# SK8_ver3.net
KiCad netlist of a schematic drawn in EAGLE
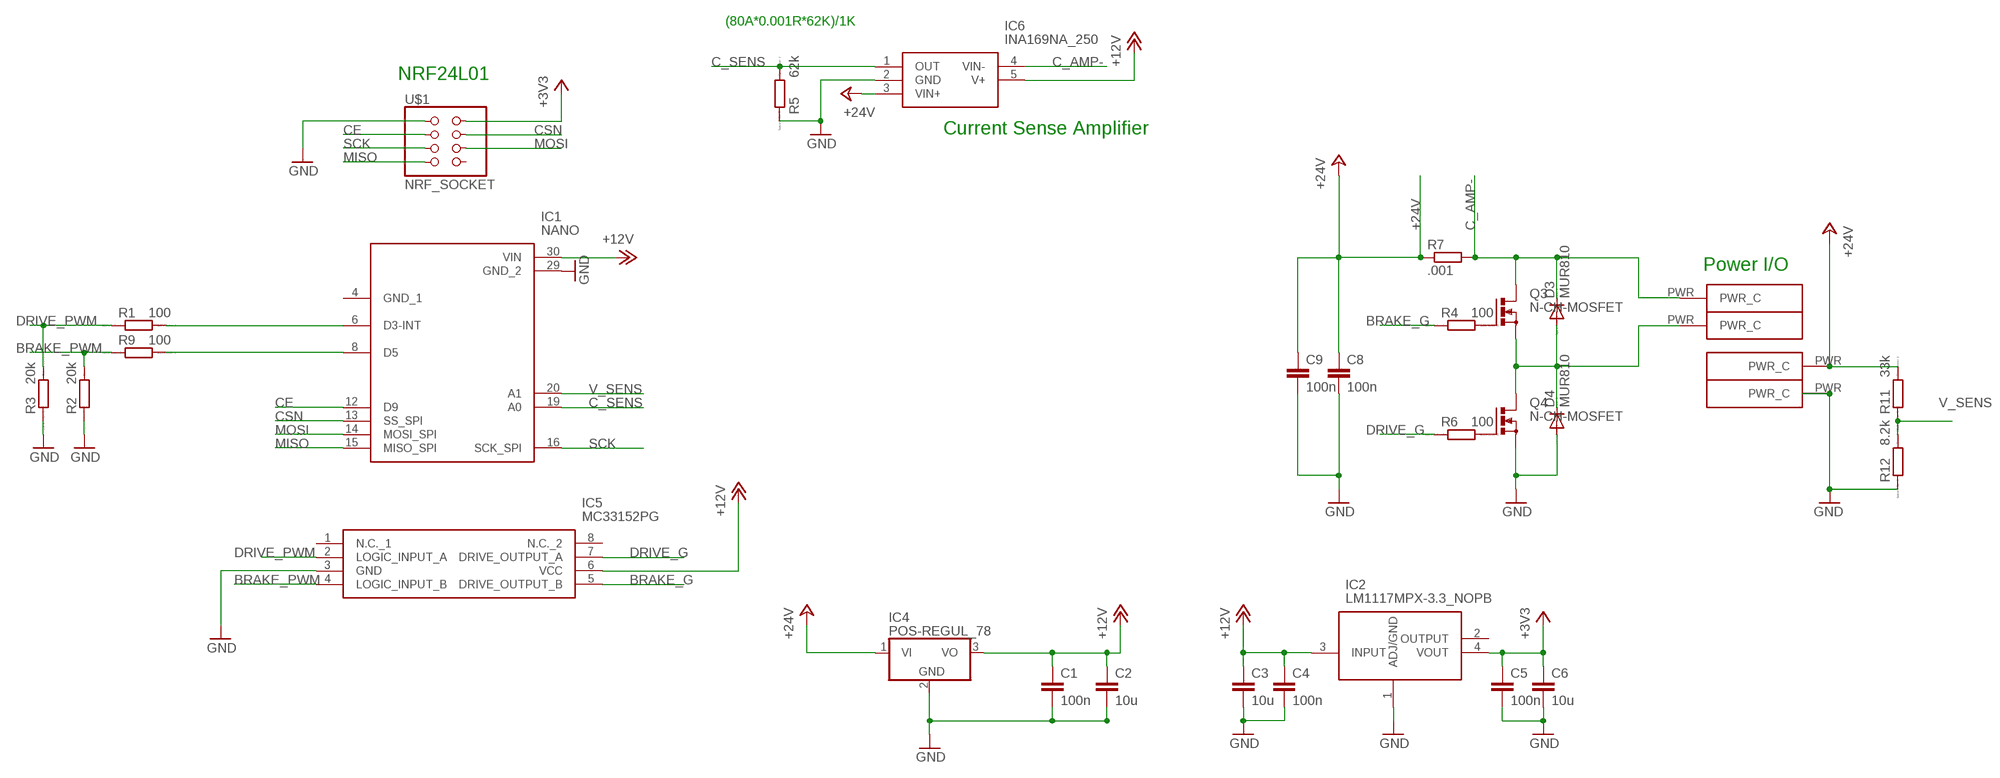
[diagram p0: schematic, sheet 1]

(export (version "E")
  (design (tool "Eeschema 10.0.6"))
  (components
    (comp (ref "C1")
      (value "100n")
      (footprint "eagle-import:C1206")
      (libsource (lib "eagle-import") (part "C-EUC1206"))
    )
    (comp (ref "C2")
      (value "10u")
      (footprint "eagle-import:C1206")
      (libsource (lib "eagle-import") (part "C-EUC1206"))
    )
    (comp (ref "C3")
      (value "10u")
      (footprint "eagle-import:C1206")
      (libsource (lib "eagle-import") (part "C-EUC1206"))
    )
    (comp (ref "C4")
      (value "100n")
      (footprint "eagle-import:C1206")
      (libsource (lib "eagle-import") (part "C-EUC1206"))
    )
    (comp (ref "C5")
      (value "100n")
      (footprint "eagle-import:C1206")
      (libsource (lib "eagle-import") (part "C-EUC1206"))
    )
    (comp (ref "C6")
      (value "10u")
      (footprint "eagle-import:C1206")
      (libsource (lib "eagle-import") (part "C-EUC1206"))
    )
    (comp (ref "C8")
      (value "100n")
      (footprint "eagle-import:C1206")
      (libsource (lib "eagle-import") (part "C-EUC1206"))
    )
    (comp (ref "C9")
      (value "100n")
      (footprint "eagle-import:C1206")
      (libsource (lib "eagle-import") (part "C-EUC1206"))
    )
    (comp (ref "D3")
      (value "MUR810")
      (footprint "eagle-import:TO220ACS")
      (libsource (lib "eagle-import") (part "MUR810"))
    )
    (comp (ref "D4")
      (value "MUR810")
      (footprint "eagle-import:TO220ACS")
      (libsource (lib "eagle-import") (part "MUR810"))
    )
    (comp (ref "IC1")
      (value "NANO")
      (footprint "eagle-import:DIP1524W102P254L4318H762Q30N")
      (fields (field (name "ARROW_PART_NUMBER") "Nano") (field (name "RS_PART_NUMBER") "6961667"))
      (libsource (lib "eagle-import") (part "NANO"))
    )
    (comp (ref "IC2")
      (value "LM1117MPX-3.3_NOPB")
      (footprint "eagle-import:SOT230P700X180-4N")
      (fields (field (name "ARROW_PART_NUMBER") "LM1117MPX-3.3/NOPB"))
      (libsource (lib "eagle-import") (part "LM1117MPX-3.3_NOPB"))
    )
    (comp (ref "IC4")
      (value "POS-REGUL_78")
      (footprint "eagle-import:TO220V")
      (libsource (lib "eagle-import") (part "POS-REGUL_78"))
    )
    (comp (ref "IC5")
      (value "MC33152PG")
      (footprint "eagle-import:DIP794W56P254L959H533Q8N")
      (fields (field (name "RS_PART_NUMBER") "7868705P"))
      (libsource (lib "eagle-import") (part "MC33152PG"))
    )
    (comp (ref "IC6")
      (value "INA169NA_250")
      (footprint "eagle-import:SOT95P280X145-5N")
      (fields (field (name "ARROW_PART_NUMBER") "INA169NA/250") (field (name "RS_PART_NUMBER") "4616586P"))
      (libsource (lib "eagle-import") (part "INA169NA_250"))
    )
    (comp (ref "Q3")
      (value "N-CH-MOSFET")
      (footprint "eagle-import:TO220BV")
      (libsource (lib "eagle-import") (part "N-CH-MOSFET"))
    )
    (comp (ref "Q4")
      (value "N-CH-MOSFET")
      (footprint "eagle-import:TO220BV")
      (libsource (lib "eagle-import") (part "N-CH-MOSFET"))
    )
    (comp (ref "R1")
      (value "100")
      (footprint "eagle-import:0204_7")
      (libsource (lib "eagle-import") (part "RESISTOR-7.5MM"))
    )
    (comp (ref "R2")
      (value "20k")
      (footprint "eagle-import:0204_7")
      (libsource (lib "eagle-import") (part "RESISTOR-7.5MM"))
    )
    (comp (ref "R3")
      (value "20k")
      (footprint "eagle-import:0204_7")
      (libsource (lib "eagle-import") (part "RESISTOR-7.5MM"))
    )
    (comp (ref "R4")
      (value "100")
      (footprint "eagle-import:0204_7")
      (libsource (lib "eagle-import") (part "RESISTOR-7.5MM"))
    )
    (comp (ref "R5")
      (value "62k")
      (footprint "eagle-import:0204_7")
      (libsource (lib "eagle-import") (part "RESISTOR-7.5MM"))
    )
    (comp (ref "R6")
      (value "100")
      (footprint "eagle-import:0204_7")
      (libsource (lib "eagle-import") (part "RESISTOR-7.5MM"))
    )
    (comp (ref "R7")
      (value ".001")
      (footprint "eagle-import:R2512")
      (libsource (lib "eagle-import") (part "R-EU_R2512"))
    )
    (comp (ref "R9")
      (value "100")
      (footprint "eagle-import:0204_7")
      (libsource (lib "eagle-import") (part "RESISTOR-7.5MM"))
    )
    (comp (ref "R11")
      (value "33k")
      (footprint "eagle-import:0204_7")
      (libsource (lib "eagle-import") (part "RESISTOR-7.5MM"))
    )
    (comp (ref "R12")
      (value "8.2k")
      (footprint "eagle-import:0204_7")
      (libsource (lib "eagle-import") (part "RESISTOR-7.5MM"))
    )
    (comp (ref "U$1")
      (value "NRF_SOCKET")
      (footprint "eagle-import:2X04")
      (libsource (lib "eagle-import") (part "NRF_SOCKET"))
    )
    (comp (ref "U$2")
      (value "POWERCONNECTOR")
      (footprint "eagle-import:SMD_PAD")
      (libsource (lib "eagle-import") (part "POWERCONNECTOR"))
    )
    (comp (ref "U$3")
      (value "POWERCONNECTOR")
      (footprint "eagle-import:SMD_PAD")
      (libsource (lib "eagle-import") (part "POWERCONNECTOR"))
    )
    (comp (ref "U$4")
      (value "POWERCONNECTOR")
      (footprint "eagle-import:SMD_PAD")
      (libsource (lib "eagle-import") (part "POWERCONNECTOR"))
    )
    (comp (ref "U$5")
      (value "POWERCONNECTOR")
      (footprint "eagle-import:SMD_PAD")
      (libsource (lib "eagle-import") (part "POWERCONNECTOR"))
    )
  )
  (nets
    (net (code "1") (name "+3V3") (class "Default")
      (node (ref "C5") (pin "1") (pinfunction "1_1") (pintype "passive"))
      (node (ref "C6") (pin "1") (pinfunction "1_1") (pintype "passive"))
      (node (ref "IC2") (pin "4") (pinfunction "VOUT_4") (pintype "bidirectional"))
      (node (ref "U$1") (pin "2") (pinfunction "2_2") (pintype "passive"))
    )
    (net (code "2") (name "+12V") (class "Default")
      (node (ref "C1") (pin "1") (pinfunction "1_1") (pintype "passive"))
      (node (ref "C2") (pin "1") (pinfunction "1_1") (pintype "passive"))
      (node (ref "C3") (pin "1") (pinfunction "1_1") (pintype "passive"))
      (node (ref "C4") (pin "1") (pinfunction "1_1") (pintype "passive"))
      (node (ref "IC1") (pin "30") (pinfunction "VIN_30") (pintype "power_in"))
      (node (ref "IC2") (pin "3") (pinfunction "INPUT_3") (pintype "bidirectional"))
      (node (ref "IC4") (pin "3") (pinfunction "VO_3") (pintype "passive"))
      (node (ref "IC5") (pin "6") (pinfunction "VCC_6") (pintype "bidirectional"))
      (node (ref "IC6") (pin "5") (pinfunction "V+_5") (pintype "bidirectional"))
    )
    (net (code "3") (name "+24V") (class "Default")
      (node (ref "C8") (pin "1") (pinfunction "1_1") (pintype "passive"))
      (node (ref "C9") (pin "1") (pinfunction "1_1") (pintype "passive"))
      (node (ref "IC4") (pin "1") (pinfunction "VI_1") (pintype "input"))
      (node (ref "IC6") (pin "3") (pinfunction "VIN+_3") (pintype "input"))
      (node (ref "R11") (pin "2") (pinfunction "2_2") (pintype "passive"))
      (node (ref "R7") (pin "1") (pinfunction "1_1") (pintype "passive"))
      (node (ref "U$4") (pin "PWR") (pinfunction "PWR_C_PWR") (pintype "bidirectional"))
    )
    (net (code "4") (name "/BRAKE_G") (class "Default")
      (node (ref "IC5") (pin "5") (pinfunction "DRIVE_OUTPUT_B_5") (pintype "bidirectional"))
      (node (ref "R4") (pin "1") (pinfunction "1_1") (pintype "passive"))
    )
    (net (code "5") (name "/BRAKE_PWM") (class "Default")
      (node (ref "IC5") (pin "4") (pinfunction "LOGIC_INPUT_B_4") (pintype "bidirectional"))
      (node (ref "R2") (pin "2") (pinfunction "2_2") (pintype "passive"))
      (node (ref "R9") (pin "1") (pinfunction "1_1") (pintype "passive"))
    )
    (net (code "6") (name "/CE") (class "Default")
      (node (ref "IC1") (pin "12") (pinfunction "D9_12") (pintype "bidirectional"))
      (node (ref "U$1") (pin "3") (pinfunction "3_3") (pintype "passive"))
    )
    (net (code "7") (name "/CSN") (class "Default")
      (node (ref "IC1") (pin "13") (pinfunction "SS_SPI_13") (pintype "bidirectional"))
      (node (ref "U$1") (pin "4") (pinfunction "4_4") (pintype "passive"))
    )
    (net (code "8") (name "/C_AMP-") (class "Default")
      (node (ref "D3") (pin "C") (pinfunction "C_C") (pintype "passive"))
      (node (ref "IC6") (pin "4") (pinfunction "VIN-_4") (pintype "input"))
      (node (ref "Q3") (pin "D") (pinfunction "D_D") (pintype "passive"))
      (node (ref "R7") (pin "2") (pinfunction "2_2") (pintype "passive"))
      (node (ref "U$2") (pin "PWR") (pinfunction "PWR_C_PWR") (pintype "bidirectional"))
    )
    (net (code "9") (name "/C_SENS") (class "Default")
      (node (ref "IC1") (pin "19") (pinfunction "A0_19") (pintype "bidirectional"))
      (node (ref "IC6") (pin "1") (pinfunction "OUT_1") (pintype "output"))
      (node (ref "R5") (pin "2") (pinfunction "2_2") (pintype "passive"))
    )
    (net (code "10") (name "/DRIVE_G") (class "Default")
      (node (ref "IC5") (pin "7") (pinfunction "DRIVE_OUTPUT_A_7") (pintype "bidirectional"))
      (node (ref "R6") (pin "1") (pinfunction "1_1") (pintype "passive"))
    )
    (net (code "11") (name "/DRIVE_PWM") (class "Default")
      (node (ref "IC5") (pin "2") (pinfunction "LOGIC_INPUT_A_2") (pintype "bidirectional"))
      (node (ref "R1") (pin "1") (pinfunction "1_1") (pintype "passive"))
      (node (ref "R3") (pin "2") (pinfunction "2_2") (pintype "passive"))
    )
    (net (code "12") (name "/GND_1") (class "Default")
      (node (ref "IC1") (pin "4") (pinfunction "GND_1_4") (pintype "power_in"))
    )
    (net (code "13") (name "/MISO") (class "Default")
      (node (ref "IC1") (pin "15") (pinfunction "MISO_SPI_15") (pintype "bidirectional"))
      (node (ref "U$1") (pin "7") (pinfunction "7_7") (pintype "passive"))
    )
    (net (code "14") (name "/MOSI") (class "Default")
      (node (ref "IC1") (pin "14") (pinfunction "MOSI_SPI_14") (pintype "bidirectional"))
      (node (ref "U$1") (pin "6") (pinfunction "6_6") (pintype "passive"))
    )
    (net (code "15") (name "/SCK") (class "Default")
      (node (ref "IC1") (pin "16") (pinfunction "SCK_SPI_16") (pintype "bidirectional"))
      (node (ref "U$1") (pin "5") (pinfunction "5_5") (pintype "passive"))
    )
    (net (code "16") (name "/V_SENS") (class "Default")
      (node (ref "IC1") (pin "20") (pinfunction "A1_20") (pintype "bidirectional"))
      (node (ref "R11") (pin "1") (pinfunction "1_1") (pintype "passive"))
      (node (ref "R12") (pin "2") (pinfunction "2_2") (pintype "passive"))
    )
    (net (code "17") (name "GND") (class "Default")
      (node (ref "C1") (pin "2") (pinfunction "2_2") (pintype "passive"))
      (node (ref "C2") (pin "2") (pinfunction "2_2") (pintype "passive"))
      (node (ref "C3") (pin "2") (pinfunction "2_2") (pintype "passive"))
      (node (ref "C4") (pin "2") (pinfunction "2_2") (pintype "passive"))
      (node (ref "C5") (pin "2") (pinfunction "2_2") (pintype "passive"))
      (node (ref "C6") (pin "2") (pinfunction "2_2") (pintype "passive"))
      (node (ref "C8") (pin "2") (pinfunction "2_2") (pintype "passive"))
      (node (ref "C9") (pin "2") (pinfunction "2_2") (pintype "passive"))
      (node (ref "D4") (pin "A") (pinfunction "A_A") (pintype "passive"))
      (node (ref "IC1") (pin "29") (pinfunction "GND_2_29") (pintype "power_in"))
      (node (ref "IC2") (pin "1") (pinfunction "ADJ/GND_1") (pintype "bidirectional"))
      (node (ref "IC4") (pin "2") (pinfunction "GND_2") (pintype "passive"))
      (node (ref "IC5") (pin "3") (pinfunction "GND_3") (pintype "bidirectional"))
      (node (ref "IC6") (pin "2") (pinfunction "GND_2") (pintype "power_in"))
      (node (ref "Q4") (pin "S") (pinfunction "S_S") (pintype "passive"))
      (node (ref "R12") (pin "1") (pinfunction "1_1") (pintype "passive"))
      (node (ref "R2") (pin "1") (pinfunction "1_1") (pintype "passive"))
      (node (ref "R3") (pin "1") (pinfunction "1_1") (pintype "passive"))
      (node (ref "R5") (pin "1") (pinfunction "1_1") (pintype "passive"))
      (node (ref "U$1") (pin "1") (pinfunction "1_1") (pintype "passive"))
      (node (ref "U$5") (pin "PWR") (pinfunction "PWR_C_PWR") (pintype "bidirectional"))
    )
    (net (code "18") (name "Net-(IC1-D3-INT)") (class "Default")
      (node (ref "IC1") (pin "6") (pinfunction "D3-INT_6") (pintype "bidirectional"))
      (node (ref "R1") (pin "2") (pinfunction "2_2") (pintype "passive"))
    )
    (net (code "19") (name "Net-(IC1-D5)") (class "Default")
      (node (ref "IC1") (pin "8") (pinfunction "D5_8") (pintype "bidirectional"))
      (node (ref "R9") (pin "2") (pinfunction "2_2") (pintype "passive"))
    )
    (net (code "20") (name "Net-(Q3-PadG)") (class "Default")
      (node (ref "Q3") (pin "G") (pinfunction "G_G") (pintype "passive"))
      (node (ref "R4") (pin "2") (pinfunction "2_2") (pintype "passive"))
    )
    (net (code "21") (name "Net-(Q4-PadG)") (class "Default")
      (node (ref "Q4") (pin "G") (pinfunction "G_G") (pintype "passive"))
      (node (ref "R6") (pin "2") (pinfunction "2_2") (pintype "passive"))
    )
    (net (code "22") (name "Net-(U$3-PWR_C)") (class "Default")
      (node (ref "D3") (pin "A") (pinfunction "A_A") (pintype "passive"))
      (node (ref "D4") (pin "C") (pinfunction "C_C") (pintype "passive"))
      (node (ref "Q3") (pin "S") (pinfunction "S_S") (pintype "passive"))
      (node (ref "Q4") (pin "D") (pinfunction "D_D") (pintype "passive"))
      (node (ref "U$3") (pin "PWR") (pinfunction "PWR_C_PWR") (pintype "bidirectional"))
    )
    (net (code "23") (name "unconnected-(IC2-OUTPUT-Pad2)") (class "Default")
      (node (ref "IC2") (pin "2") (pinfunction "OUTPUT_2") (pintype "bidirectional"))
    )
    (net (code "24") (name "unconnected-(IC5-N.C._1-Pad1)") (class "Default")
      (node (ref "IC5") (pin "1") (pinfunction "N.C._1_1") (pintype "bidirectional"))
    )
    (net (code "25") (name "unconnected-(IC5-N.C._2-Pad8)") (class "Default")
      (node (ref "IC5") (pin "8") (pinfunction "N.C._2_8") (pintype "bidirectional"))
    )
    (net (code "26") (name "unconnected-(U$1-Pad8)") (class "Default")
      (node (ref "U$1") (pin "8") (pinfunction "8_8") (pintype "passive"))
    )
  )
)
